# IR4427.net
KiCad netlist of a schematic drawn in EAGLE
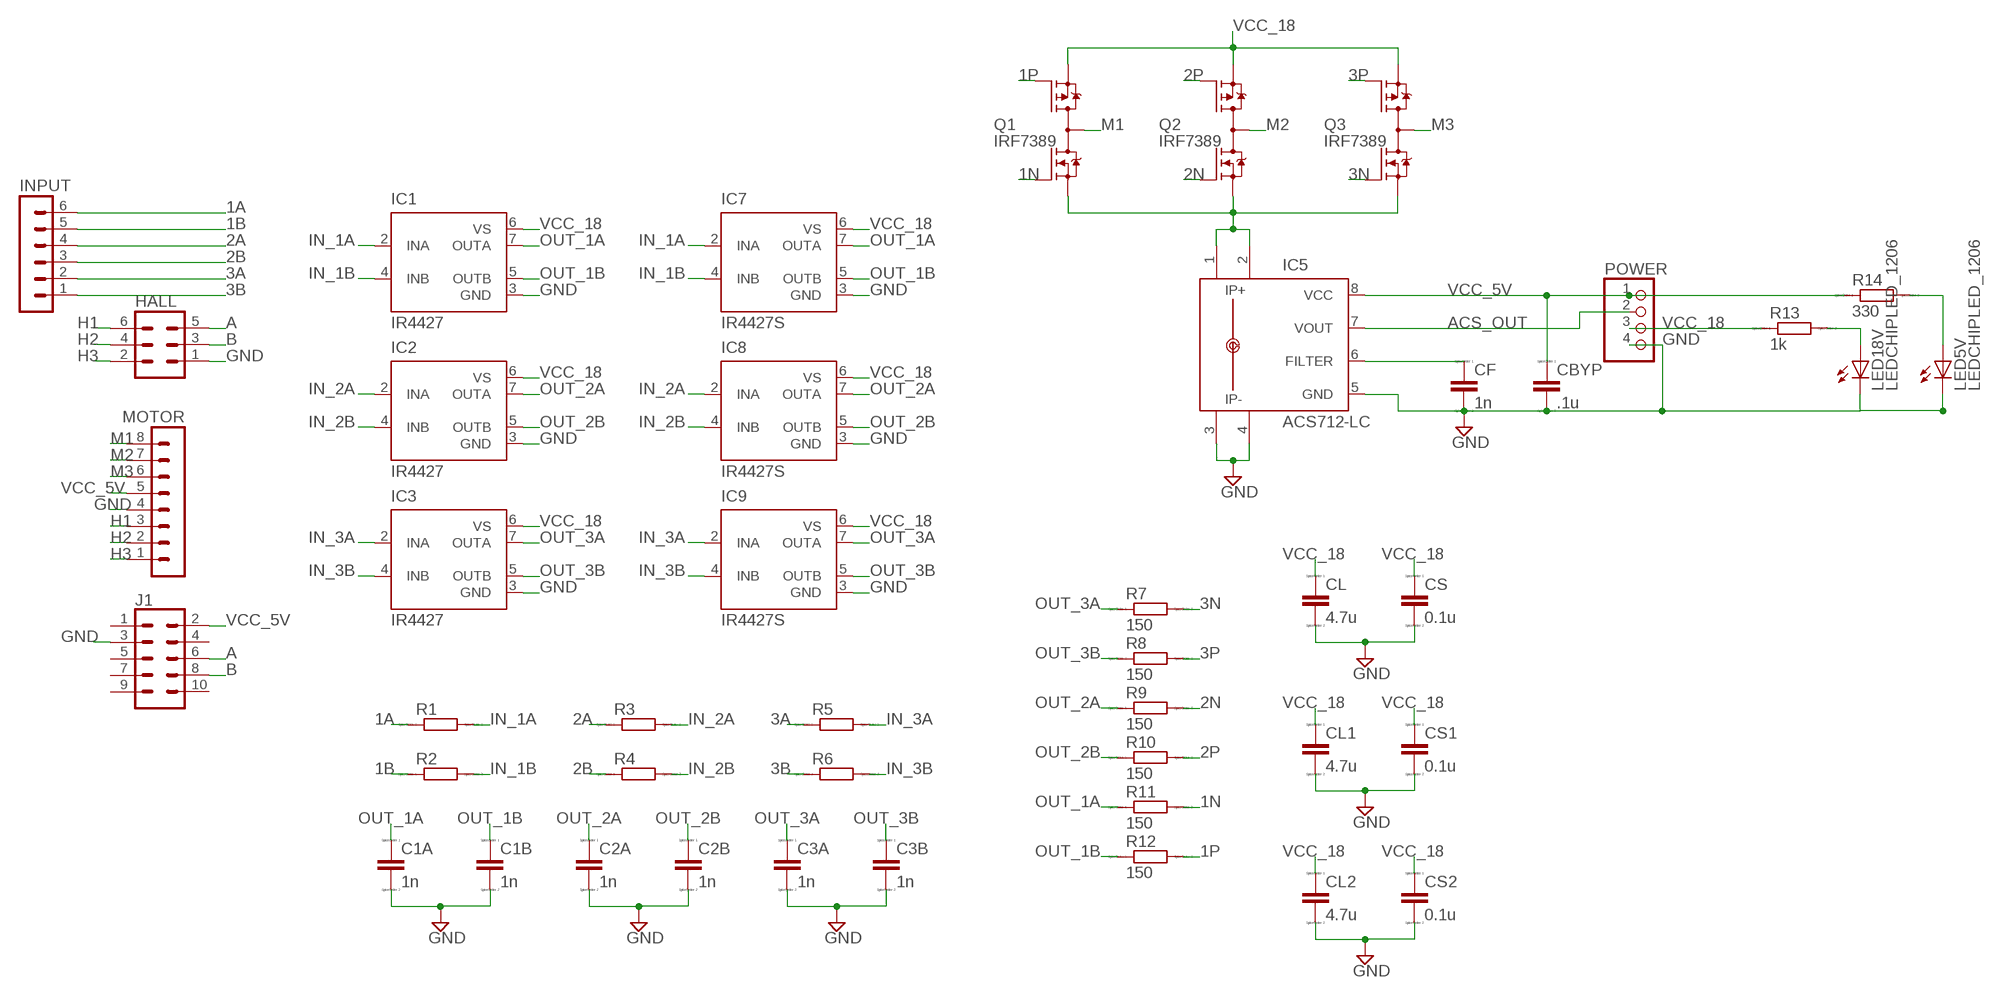
[diagram p0: schematic, sheet 1]

(export (version "E")
  (design (tool "Eeschema 10.0.6"))
  (components
    (comp (ref "C1A")
      (value "1n")
      (footprint "eagle-import:C1206")
      (libsource (lib "eagle-import") (part "CC1206"))
    )
    (comp (ref "C1B")
      (value "1n")
      (footprint "eagle-import:C1206")
      (libsource (lib "eagle-import") (part "CC1206"))
    )
    (comp (ref "C2A")
      (value "1n")
      (footprint "eagle-import:C1206")
      (libsource (lib "eagle-import") (part "CC1206"))
    )
    (comp (ref "C2B")
      (value "1n")
      (footprint "eagle-import:C1206")
      (libsource (lib "eagle-import") (part "CC1206"))
    )
    (comp (ref "C3A")
      (value "1n")
      (footprint "eagle-import:C1206")
      (libsource (lib "eagle-import") (part "CC1206"))
    )
    (comp (ref "C3B")
      (value "1n")
      (footprint "eagle-import:C1206")
      (libsource (lib "eagle-import") (part "CC1206"))
    )
    (comp (ref "CBYP")
      (value ".1u")
      (footprint "eagle-import:C1206")
      (libsource (lib "eagle-import") (part "CC1206"))
    )
    (comp (ref "CF")
      (value "1n")
      (footprint "eagle-import:C1206")
      (libsource (lib "eagle-import") (part "CC1206"))
    )
    (comp (ref "CL")
      (value "4.7u")
      (footprint "eagle-import:C1206")
      (libsource (lib "eagle-import") (part "CC1206"))
    )
    (comp (ref "CL1")
      (value "4.7u")
      (footprint "eagle-import:C1206")
      (libsource (lib "eagle-import") (part "CC1206"))
    )
    (comp (ref "CL2")
      (value "4.7u")
      (footprint "eagle-import:C1206")
      (libsource (lib "eagle-import") (part "CC1206"))
    )
    (comp (ref "CS")
      (value "0.1u")
      (footprint "eagle-import:C1206")
      (libsource (lib "eagle-import") (part "CC1206"))
    )
    (comp (ref "CS1")
      (value "0.1u")
      (footprint "eagle-import:C1206")
      (libsource (lib "eagle-import") (part "CC1206"))
    )
    (comp (ref "CS2")
      (value "0.1u")
      (footprint "eagle-import:C1206")
      (libsource (lib "eagle-import") (part "CC1206"))
    )
    (comp (ref "HALL")
      (value "MA03-2")
      (footprint "eagle-import:MA03-2")
      (libsource (lib "eagle-import") (part "MA03-2"))
    )
    (comp (ref "IC1")
      (value "IR4427")
      (footprint "eagle-import:DIL08")
      (fields (field (name "MF") "INTERNATIONAL RECTIFIER(IR)"))
      (libsource (lib "eagle-import") (part "IR4427"))
    )
    (comp (ref "IC2")
      (value "IR4427")
      (footprint "eagle-import:DIL08")
      (fields (field (name "MF") "INTERNATIONAL RECTIFIER(IR)"))
      (libsource (lib "eagle-import") (part "IR4427"))
    )
    (comp (ref "IC3")
      (value "IR4427")
      (footprint "eagle-import:DIL08")
      (fields (field (name "MF") "INTERNATIONAL RECTIFIER(IR)"))
      (libsource (lib "eagle-import") (part "IR4427"))
    )
    (comp (ref "IC5")
      (value "ACS712-LC")
      (footprint "eagle-import:SOIC8")
      (libsource (lib "eagle-import") (part "ACS712-LC"))
    )
    (comp (ref "IC7")
      (value "IR4427S")
      (footprint "eagle-import:SO08")
      (fields (field (name "MF") "INTERNATIONAL RECTIFIER(IR)") (field (name "MPN") "IR4427STRPBF"))
      (libsource (lib "eagle-import") (part "IR4427S"))
    )
    (comp (ref "IC8")
      (value "IR4427S")
      (footprint "eagle-import:SO08")
      (fields (field (name "MF") "INTERNATIONAL RECTIFIER(IR)") (field (name "MPN") "IR4427STRPBF"))
      (libsource (lib "eagle-import") (part "IR4427S"))
    )
    (comp (ref "IC9")
      (value "IR4427S")
      (footprint "eagle-import:SO08")
      (fields (field (name "MF") "INTERNATIONAL RECTIFIER(IR)") (field (name "MPN") "IR4427STRPBF"))
      (libsource (lib "eagle-import") (part "IR4427S"))
    )
    (comp (ref "INPUT")
      (value "MA06-1")
      (footprint "eagle-import:MA06-1")
      (libsource (lib "eagle-import") (part "MA06-1"))
    )
    (comp (ref "J1")
      (value "CONN_05X2SHD_LOCK")
      (footprint "eagle-import:2X5-SHROUDED_LOCK")
      (libsource (lib "eagle-import") (part "CONN_05X2SHD_LOCK"))
    )
    (comp (ref "LED5V")
      (value "LEDCHIPLED_1206")
      (footprint "eagle-import:CHIPLED_1206")
      (libsource (lib "eagle-import") (part "LEDCHIPLED_1206"))
    )
    (comp (ref "LED18V")
      (value "LEDCHIPLED_1206")
      (footprint "eagle-import:CHIPLED_1206")
      (libsource (lib "eagle-import") (part "LEDCHIPLED_1206"))
    )
    (comp (ref "MOTOR")
      (value "MA08-1")
      (footprint "eagle-import:MA08-1")
      (libsource (lib "eagle-import") (part "MA08-1"))
    )
    (comp (ref "POWER")
      (value "PINHD-1X4")
      (footprint "eagle-import:1X04")
      (libsource (lib "eagle-import") (part "PINHD-1X4"))
    )
    (comp (ref "Q1")
      (value "IRF7389")
      (footprint "eagle-import:SO08-IRF")
      (libsource (lib "eagle-import") (part "IRF7389"))
    )
    (comp (ref "Q2")
      (value "IRF7389")
      (footprint "eagle-import:SO08-IRF")
      (libsource (lib "eagle-import") (part "IRF7389"))
    )
    (comp (ref "Q3")
      (value "IRF7389")
      (footprint "eagle-import:SO08-IRF")
      (libsource (lib "eagle-import") (part "IRF7389"))
    )
    (comp (ref "R1")
      (value "RR1206")
      (footprint "eagle-import:R1206")
      (libsource (lib "eagle-import") (part "RR1206"))
    )
    (comp (ref "R2")
      (value "RR1206")
      (footprint "eagle-import:R1206")
      (libsource (lib "eagle-import") (part "RR1206"))
    )
    (comp (ref "R3")
      (value "RR1206")
      (footprint "eagle-import:R1206")
      (libsource (lib "eagle-import") (part "RR1206"))
    )
    (comp (ref "R4")
      (value "RR1206")
      (footprint "eagle-import:R1206")
      (libsource (lib "eagle-import") (part "RR1206"))
    )
    (comp (ref "R5")
      (value "RR1206")
      (footprint "eagle-import:R1206")
      (libsource (lib "eagle-import") (part "RR1206"))
    )
    (comp (ref "R6")
      (value "RR1206")
      (footprint "eagle-import:R1206")
      (libsource (lib "eagle-import") (part "RR1206"))
    )
    (comp (ref "R7")
      (value "150")
      (footprint "eagle-import:R1206")
      (libsource (lib "eagle-import") (part "RR1206"))
    )
    (comp (ref "R8")
      (value "150")
      (footprint "eagle-import:R1206")
      (libsource (lib "eagle-import") (part "RR1206"))
    )
    (comp (ref "R9")
      (value "150")
      (footprint "eagle-import:R1206")
      (libsource (lib "eagle-import") (part "RR1206"))
    )
    (comp (ref "R10")
      (value "150")
      (footprint "eagle-import:R1206")
      (libsource (lib "eagle-import") (part "RR1206"))
    )
    (comp (ref "R11")
      (value "150")
      (footprint "eagle-import:R1206")
      (libsource (lib "eagle-import") (part "RR1206"))
    )
    (comp (ref "R12")
      (value "150")
      (footprint "eagle-import:R1206")
      (libsource (lib "eagle-import") (part "RR1206"))
    )
    (comp (ref "R13")
      (value "1k")
      (footprint "eagle-import:R1206")
      (libsource (lib "eagle-import") (part "RR1206"))
    )
    (comp (ref "R14")
      (value "330")
      (footprint "eagle-import:R1206")
      (libsource (lib "eagle-import") (part "RR1206"))
    )
  )
  (nets
    (net (code "1") (name "/1A") (class "Default")
      (node (ref "INPUT") (pin "6") (pinfunction "6_6") (pintype "passive"))
      (node (ref "R1") (pin "1") (pinfunction "1_1") (pintype "passive"))
    )
    (net (code "2") (name "/1B") (class "Default")
      (node (ref "INPUT") (pin "5") (pinfunction "5_5") (pintype "passive"))
      (node (ref "R2") (pin "1") (pinfunction "1_1") (pintype "passive"))
    )
    (net (code "3") (name "/1N") (class "Default")
      (node (ref "Q1") (pin "2") (pinfunction "N-G_2") (pintype "passive"))
      (node (ref "R11") (pin "2") (pinfunction "2_2") (pintype "passive"))
    )
    (net (code "4") (name "/1P") (class "Default")
      (node (ref "Q1") (pin "4") (pinfunction "P-G_4") (pintype "passive"))
      (node (ref "R12") (pin "2") (pinfunction "2_2") (pintype "passive"))
    )
    (net (code "5") (name "/2A") (class "Default")
      (node (ref "INPUT") (pin "4") (pinfunction "4_4") (pintype "passive"))
      (node (ref "R3") (pin "1") (pinfunction "1_1") (pintype "passive"))
    )
    (net (code "6") (name "/2B") (class "Default")
      (node (ref "INPUT") (pin "3") (pinfunction "3_3") (pintype "passive"))
      (node (ref "R4") (pin "1") (pinfunction "1_1") (pintype "passive"))
    )
    (net (code "7") (name "/2N") (class "Default")
      (node (ref "Q2") (pin "2") (pinfunction "N-G_2") (pintype "passive"))
      (node (ref "R9") (pin "2") (pinfunction "2_2") (pintype "passive"))
    )
    (net (code "8") (name "/2P") (class "Default")
      (node (ref "Q2") (pin "4") (pinfunction "P-G_4") (pintype "passive"))
      (node (ref "R10") (pin "2") (pinfunction "2_2") (pintype "passive"))
    )
    (net (code "9") (name "/3A") (class "Default")
      (node (ref "INPUT") (pin "2") (pinfunction "2_2") (pintype "passive"))
      (node (ref "R5") (pin "1") (pinfunction "1_1") (pintype "passive"))
    )
    (net (code "10") (name "/3B") (class "Default")
      (node (ref "INPUT") (pin "1") (pinfunction "1_1") (pintype "passive"))
      (node (ref "R6") (pin "1") (pinfunction "1_1") (pintype "passive"))
    )
    (net (code "11") (name "/3N") (class "Default")
      (node (ref "Q3") (pin "2") (pinfunction "N-G_2") (pintype "passive"))
      (node (ref "R7") (pin "2") (pinfunction "2_2") (pintype "passive"))
    )
    (net (code "12") (name "/3P") (class "Default")
      (node (ref "Q3") (pin "4") (pinfunction "P-G_4") (pintype "passive"))
      (node (ref "R8") (pin "2") (pinfunction "2_2") (pintype "passive"))
    )
    (net (code "13") (name "/A") (class "Default")
      (node (ref "HALL") (pin "5") (pinfunction "5_5") (pintype "passive"))
      (node (ref "J1") (pin "6") (pinfunction "6_6") (pintype "passive"))
    )
    (net (code "14") (name "/ACS_OUT") (class "Default")
      (node (ref "IC5") (pin "7") (pinfunction "VOUT_7") (pintype "output"))
      (node (ref "POWER") (pin "2") (pinfunction "2_2") (pintype "passive"))
    )
    (net (code "15") (name "/B") (class "Default")
      (node (ref "HALL") (pin "3") (pinfunction "3_3") (pintype "passive"))
      (node (ref "J1") (pin "8") (pinfunction "8_8") (pintype "passive"))
    )
    (net (code "16") (name "/H1") (class "Default")
      (node (ref "HALL") (pin "6") (pinfunction "6_6") (pintype "passive"))
      (node (ref "MOTOR") (pin "3") (pinfunction "3_3") (pintype "passive"))
    )
    (net (code "17") (name "/H2") (class "Default")
      (node (ref "HALL") (pin "4") (pinfunction "4_4") (pintype "passive"))
      (node (ref "MOTOR") (pin "2") (pinfunction "2_2") (pintype "passive"))
    )
    (net (code "18") (name "/H3") (class "Default")
      (node (ref "HALL") (pin "2") (pinfunction "2_2") (pintype "passive"))
      (node (ref "MOTOR") (pin "1") (pinfunction "1_1") (pintype "passive"))
    )
    (net (code "19") (name "/IN_1A") (class "Default")
      (node (ref "IC1") (pin "2") (pinfunction "INA_2") (pintype "input"))
      (node (ref "IC7") (pin "2") (pinfunction "INA_2") (pintype "input"))
      (node (ref "R1") (pin "2") (pinfunction "2_2") (pintype "passive"))
    )
    (net (code "20") (name "/IN_1B") (class "Default")
      (node (ref "IC1") (pin "4") (pinfunction "INB_4") (pintype "input"))
      (node (ref "IC7") (pin "4") (pinfunction "INB_4") (pintype "input"))
      (node (ref "R2") (pin "2") (pinfunction "2_2") (pintype "passive"))
    )
    (net (code "21") (name "/IN_2A") (class "Default")
      (node (ref "IC2") (pin "2") (pinfunction "INA_2") (pintype "input"))
      (node (ref "IC8") (pin "2") (pinfunction "INA_2") (pintype "input"))
      (node (ref "R3") (pin "2") (pinfunction "2_2") (pintype "passive"))
    )
    (net (code "22") (name "/IN_2B") (class "Default")
      (node (ref "IC2") (pin "4") (pinfunction "INB_4") (pintype "input"))
      (node (ref "IC8") (pin "4") (pinfunction "INB_4") (pintype "input"))
      (node (ref "R4") (pin "2") (pinfunction "2_2") (pintype "passive"))
    )
    (net (code "23") (name "/IN_3A") (class "Default")
      (node (ref "IC3") (pin "2") (pinfunction "INA_2") (pintype "input"))
      (node (ref "IC9") (pin "2") (pinfunction "INA_2") (pintype "input"))
      (node (ref "R5") (pin "2") (pinfunction "2_2") (pintype "passive"))
    )
    (net (code "24") (name "/IN_3B") (class "Default")
      (node (ref "IC3") (pin "4") (pinfunction "INB_4") (pintype "input"))
      (node (ref "IC9") (pin "4") (pinfunction "INB_4") (pintype "input"))
      (node (ref "R6") (pin "2") (pinfunction "2_2") (pintype "passive"))
    )
    (net (code "25") (name "/M1") (class "Default")
      (node (ref "MOTOR") (pin "8") (pinfunction "8_8") (pintype "passive"))
      (node (ref "Q1") (pin "5") (pinfunction "D_5") (pintype "passive"))
      (node (ref "Q1") (pin "6") (pinfunction "D_6") (pintype "passive"))
      (node (ref "Q1") (pin "7") (pinfunction "D_7") (pintype "passive"))
      (node (ref "Q1") (pin "8") (pinfunction "D_8") (pintype "passive"))
    )
    (net (code "26") (name "/M2") (class "Default")
      (node (ref "MOTOR") (pin "7") (pinfunction "7_7") (pintype "passive"))
      (node (ref "Q2") (pin "5") (pinfunction "D_5") (pintype "passive"))
      (node (ref "Q2") (pin "6") (pinfunction "D_6") (pintype "passive"))
      (node (ref "Q2") (pin "7") (pinfunction "D_7") (pintype "passive"))
      (node (ref "Q2") (pin "8") (pinfunction "D_8") (pintype "passive"))
    )
    (net (code "27") (name "/M3") (class "Default")
      (node (ref "MOTOR") (pin "6") (pinfunction "6_6") (pintype "passive"))
      (node (ref "Q3") (pin "5") (pinfunction "D_5") (pintype "passive"))
      (node (ref "Q3") (pin "6") (pinfunction "D_6") (pintype "passive"))
      (node (ref "Q3") (pin "7") (pinfunction "D_7") (pintype "passive"))
      (node (ref "Q3") (pin "8") (pinfunction "D_8") (pintype "passive"))
    )
    (net (code "28") (name "/OUT_1A") (class "Default")
      (node (ref "C1A") (pin "1") (pinfunction "1_1") (pintype "passive"))
      (node (ref "IC1") (pin "7") (pinfunction "OUTA_7") (pintype "output"))
      (node (ref "IC7") (pin "7") (pinfunction "OUTA_7") (pintype "output"))
      (node (ref "R11") (pin "1") (pinfunction "1_1") (pintype "passive"))
    )
    (net (code "29") (name "/OUT_1B") (class "Default")
      (node (ref "C1B") (pin "1") (pinfunction "1_1") (pintype "passive"))
      (node (ref "IC1") (pin "5") (pinfunction "OUTB_5") (pintype "output"))
      (node (ref "IC7") (pin "5") (pinfunction "OUTB_5") (pintype "output"))
      (node (ref "R12") (pin "1") (pinfunction "1_1") (pintype "passive"))
    )
    (net (code "30") (name "/OUT_2A") (class "Default")
      (node (ref "C2A") (pin "1") (pinfunction "1_1") (pintype "passive"))
      (node (ref "IC2") (pin "7") (pinfunction "OUTA_7") (pintype "output"))
      (node (ref "IC8") (pin "7") (pinfunction "OUTA_7") (pintype "output"))
      (node (ref "R9") (pin "1") (pinfunction "1_1") (pintype "passive"))
    )
    (net (code "31") (name "/OUT_2B") (class "Default")
      (node (ref "C2B") (pin "1") (pinfunction "1_1") (pintype "passive"))
      (node (ref "IC2") (pin "5") (pinfunction "OUTB_5") (pintype "output"))
      (node (ref "IC8") (pin "5") (pinfunction "OUTB_5") (pintype "output"))
      (node (ref "R10") (pin "1") (pinfunction "1_1") (pintype "passive"))
    )
    (net (code "32") (name "/OUT_3A") (class "Default")
      (node (ref "C3A") (pin "1") (pinfunction "1_1") (pintype "passive"))
      (node (ref "IC3") (pin "7") (pinfunction "OUTA_7") (pintype "output"))
      (node (ref "IC9") (pin "7") (pinfunction "OUTA_7") (pintype "output"))
      (node (ref "R7") (pin "1") (pinfunction "1_1") (pintype "passive"))
    )
    (net (code "33") (name "/OUT_3B") (class "Default")
      (node (ref "C3B") (pin "1") (pinfunction "1_1") (pintype "passive"))
      (node (ref "IC3") (pin "5") (pinfunction "OUTB_5") (pintype "output"))
      (node (ref "IC9") (pin "5") (pinfunction "OUTB_5") (pintype "output"))
      (node (ref "R8") (pin "1") (pinfunction "1_1") (pintype "passive"))
    )
    (net (code "34") (name "/VCC_5V") (class "Default")
      (node (ref "CBYP") (pin "1") (pinfunction "1_1") (pintype "passive"))
      (node (ref "IC5") (pin "8") (pinfunction "VCC_8") (pintype "power_in"))
      (node (ref "J1") (pin "2") (pinfunction "2_2") (pintype "passive"))
      (node (ref "MOTOR") (pin "5") (pinfunction "5_5") (pintype "passive"))
      (node (ref "POWER") (pin "1") (pinfunction "1_1") (pintype "passive"))
      (node (ref "R14") (pin "1") (pinfunction "1_1") (pintype "passive"))
    )
    (net (code "35") (name "/VCC_18") (class "Default")
      (node (ref "CL") (pin "1") (pinfunction "1_1") (pintype "passive"))
      (node (ref "CL1") (pin "1") (pinfunction "1_1") (pintype "passive"))
      (node (ref "CL2") (pin "1") (pinfunction "1_1") (pintype "passive"))
      (node (ref "CS") (pin "1") (pinfunction "1_1") (pintype "passive"))
      (node (ref "CS1") (pin "1") (pinfunction "1_1") (pintype "passive"))
      (node (ref "CS2") (pin "1") (pinfunction "1_1") (pintype "passive"))
      (node (ref "IC1") (pin "6") (pinfunction "VS_6") (pintype "power_in"))
      (node (ref "IC2") (pin "6") (pinfunction "VS_6") (pintype "power_in"))
      (node (ref "IC3") (pin "6") (pinfunction "VS_6") (pintype "power_in"))
      (node (ref "IC7") (pin "6") (pinfunction "VS_6") (pintype "power_in"))
      (node (ref "IC8") (pin "6") (pinfunction "VS_6") (pintype "power_in"))
      (node (ref "IC9") (pin "6") (pinfunction "VS_6") (pintype "power_in"))
      (node (ref "POWER") (pin "3") (pinfunction "3_3") (pintype "passive"))
      (node (ref "Q1") (pin "3") (pinfunction "P-S_3") (pintype "passive"))
      (node (ref "Q2") (pin "3") (pinfunction "P-S_3") (pintype "passive"))
      (node (ref "Q3") (pin "3") (pinfunction "P-S_3") (pintype "passive"))
      (node (ref "R13") (pin "1") (pinfunction "1_1") (pintype "passive"))
    )
    (net (code "36") (name "GND") (class "Default")
      (node (ref "C1A") (pin "2") (pinfunction "2_2") (pintype "passive"))
      (node (ref "C1B") (pin "2") (pinfunction "2_2") (pintype "passive"))
      (node (ref "C2A") (pin "2") (pinfunction "2_2") (pintype "passive"))
      (node (ref "C2B") (pin "2") (pinfunction "2_2") (pintype "passive"))
      (node (ref "C3A") (pin "2") (pinfunction "2_2") (pintype "passive"))
      (node (ref "C3B") (pin "2") (pinfunction "2_2") (pintype "passive"))
      (node (ref "CBYP") (pin "2") (pinfunction "2_2") (pintype "passive"))
      (node (ref "CF") (pin "2") (pinfunction "2_2") (pintype "passive"))
      (node (ref "CL") (pin "2") (pinfunction "2_2") (pintype "passive"))
      (node (ref "CL1") (pin "2") (pinfunction "2_2") (pintype "passive"))
      (node (ref "CL2") (pin "2") (pinfunction "2_2") (pintype "passive"))
      (node (ref "CS") (pin "2") (pinfunction "2_2") (pintype "passive"))
      (node (ref "CS1") (pin "2") (pinfunction "2_2") (pintype "passive"))
      (node (ref "CS2") (pin "2") (pinfunction "2_2") (pintype "passive"))
      (node (ref "HALL") (pin "1") (pinfunction "1_1") (pintype "passive"))
      (node (ref "IC1") (pin "3") (pinfunction "GND_3") (pintype "power_in"))
      (node (ref "IC2") (pin "3") (pinfunction "GND_3") (pintype "power_in"))
      (node (ref "IC3") (pin "3") (pinfunction "GND_3") (pintype "power_in"))
      (node (ref "IC5") (pin "3") (pinfunction "IP-_3") (pintype "passive"))
      (node (ref "IC5") (pin "4") (pinfunction "IP-1_4") (pintype "passive"))
      (node (ref "IC5") (pin "5") (pinfunction "GND_5") (pintype "power_in"))
      (node (ref "IC7") (pin "3") (pinfunction "GND_3") (pintype "power_in"))
      (node (ref "IC8") (pin "3") (pinfunction "GND_3") (pintype "power_in"))
      (node (ref "IC9") (pin "3") (pinfunction "GND_3") (pintype "power_in"))
      (node (ref "J1") (pin "3") (pinfunction "3_3") (pintype "passive"))
      (node (ref "LED18V") (pin "C") (pinfunction "C_C") (pintype "passive"))
      (node (ref "LED5V") (pin "C") (pinfunction "C_C") (pintype "passive"))
      (node (ref "MOTOR") (pin "4") (pinfunction "4_4") (pintype "passive"))
      (node (ref "POWER") (pin "4") (pinfunction "4_4") (pintype "passive"))
    )
    (net (code "37") (name "Net-(IC5-FILTER)") (class "Default")
      (node (ref "CF") (pin "1") (pinfunction "1_1") (pintype "passive"))
      (node (ref "IC5") (pin "6") (pinfunction "FILTER_6") (pintype "bidirectional"))
    )
    (net (code "38") (name "Net-(IC5-IP+)") (class "Default")
      (node (ref "IC5") (pin "1") (pinfunction "IP+_1") (pintype "passive"))
      (node (ref "IC5") (pin "2") (pinfunction "IP+1_2") (pintype "passive"))
      (node (ref "Q1") (pin "1") (pinfunction "N-S_1") (pintype "passive"))
      (node (ref "Q2") (pin "1") (pinfunction "N-S_1") (pintype "passive"))
      (node (ref "Q3") (pin "1") (pinfunction "N-S_1") (pintype "passive"))
    )
    (net (code "39") (name "Net-(LED5V-PadA)") (class "Default")
      (node (ref "LED5V") (pin "A") (pinfunction "A_A") (pintype "passive"))
      (node (ref "R14") (pin "2") (pinfunction "2_2") (pintype "passive"))
    )
    (net (code "40") (name "Net-(LED18V-PadA)") (class "Default")
      (node (ref "LED18V") (pin "A") (pinfunction "A_A") (pintype "passive"))
      (node (ref "R13") (pin "2") (pinfunction "2_2") (pintype "passive"))
    )
    (net (code "41") (name "unconnected-(J1-Pad1)") (class "Default")
      (node (ref "J1") (pin "1") (pinfunction "1_1") (pintype "passive"))
    )
    (net (code "42") (name "unconnected-(J1-Pad4)") (class "Default")
      (node (ref "J1") (pin "4") (pinfunction "4_4") (pintype "passive"))
    )
    (net (code "43") (name "unconnected-(J1-Pad5)") (class "Default")
      (node (ref "J1") (pin "5") (pinfunction "5_5") (pintype "passive"))
    )
    (net (code "44") (name "unconnected-(J1-Pad7)") (class "Default")
      (node (ref "J1") (pin "7") (pinfunction "7_7") (pintype "passive"))
    )
    (net (code "45") (name "unconnected-(J1-Pad9)") (class "Default")
      (node (ref "J1") (pin "9") (pinfunction "9_9") (pintype "passive"))
    )
    (net (code "46") (name "unconnected-(J1-Pad10)") (class "Default")
      (node (ref "J1") (pin "10") (pinfunction "10_10") (pintype "passive"))
    )
  )
)
